# drum_circuits.net
KiCad netlist of a schematic drawn in EAGLE
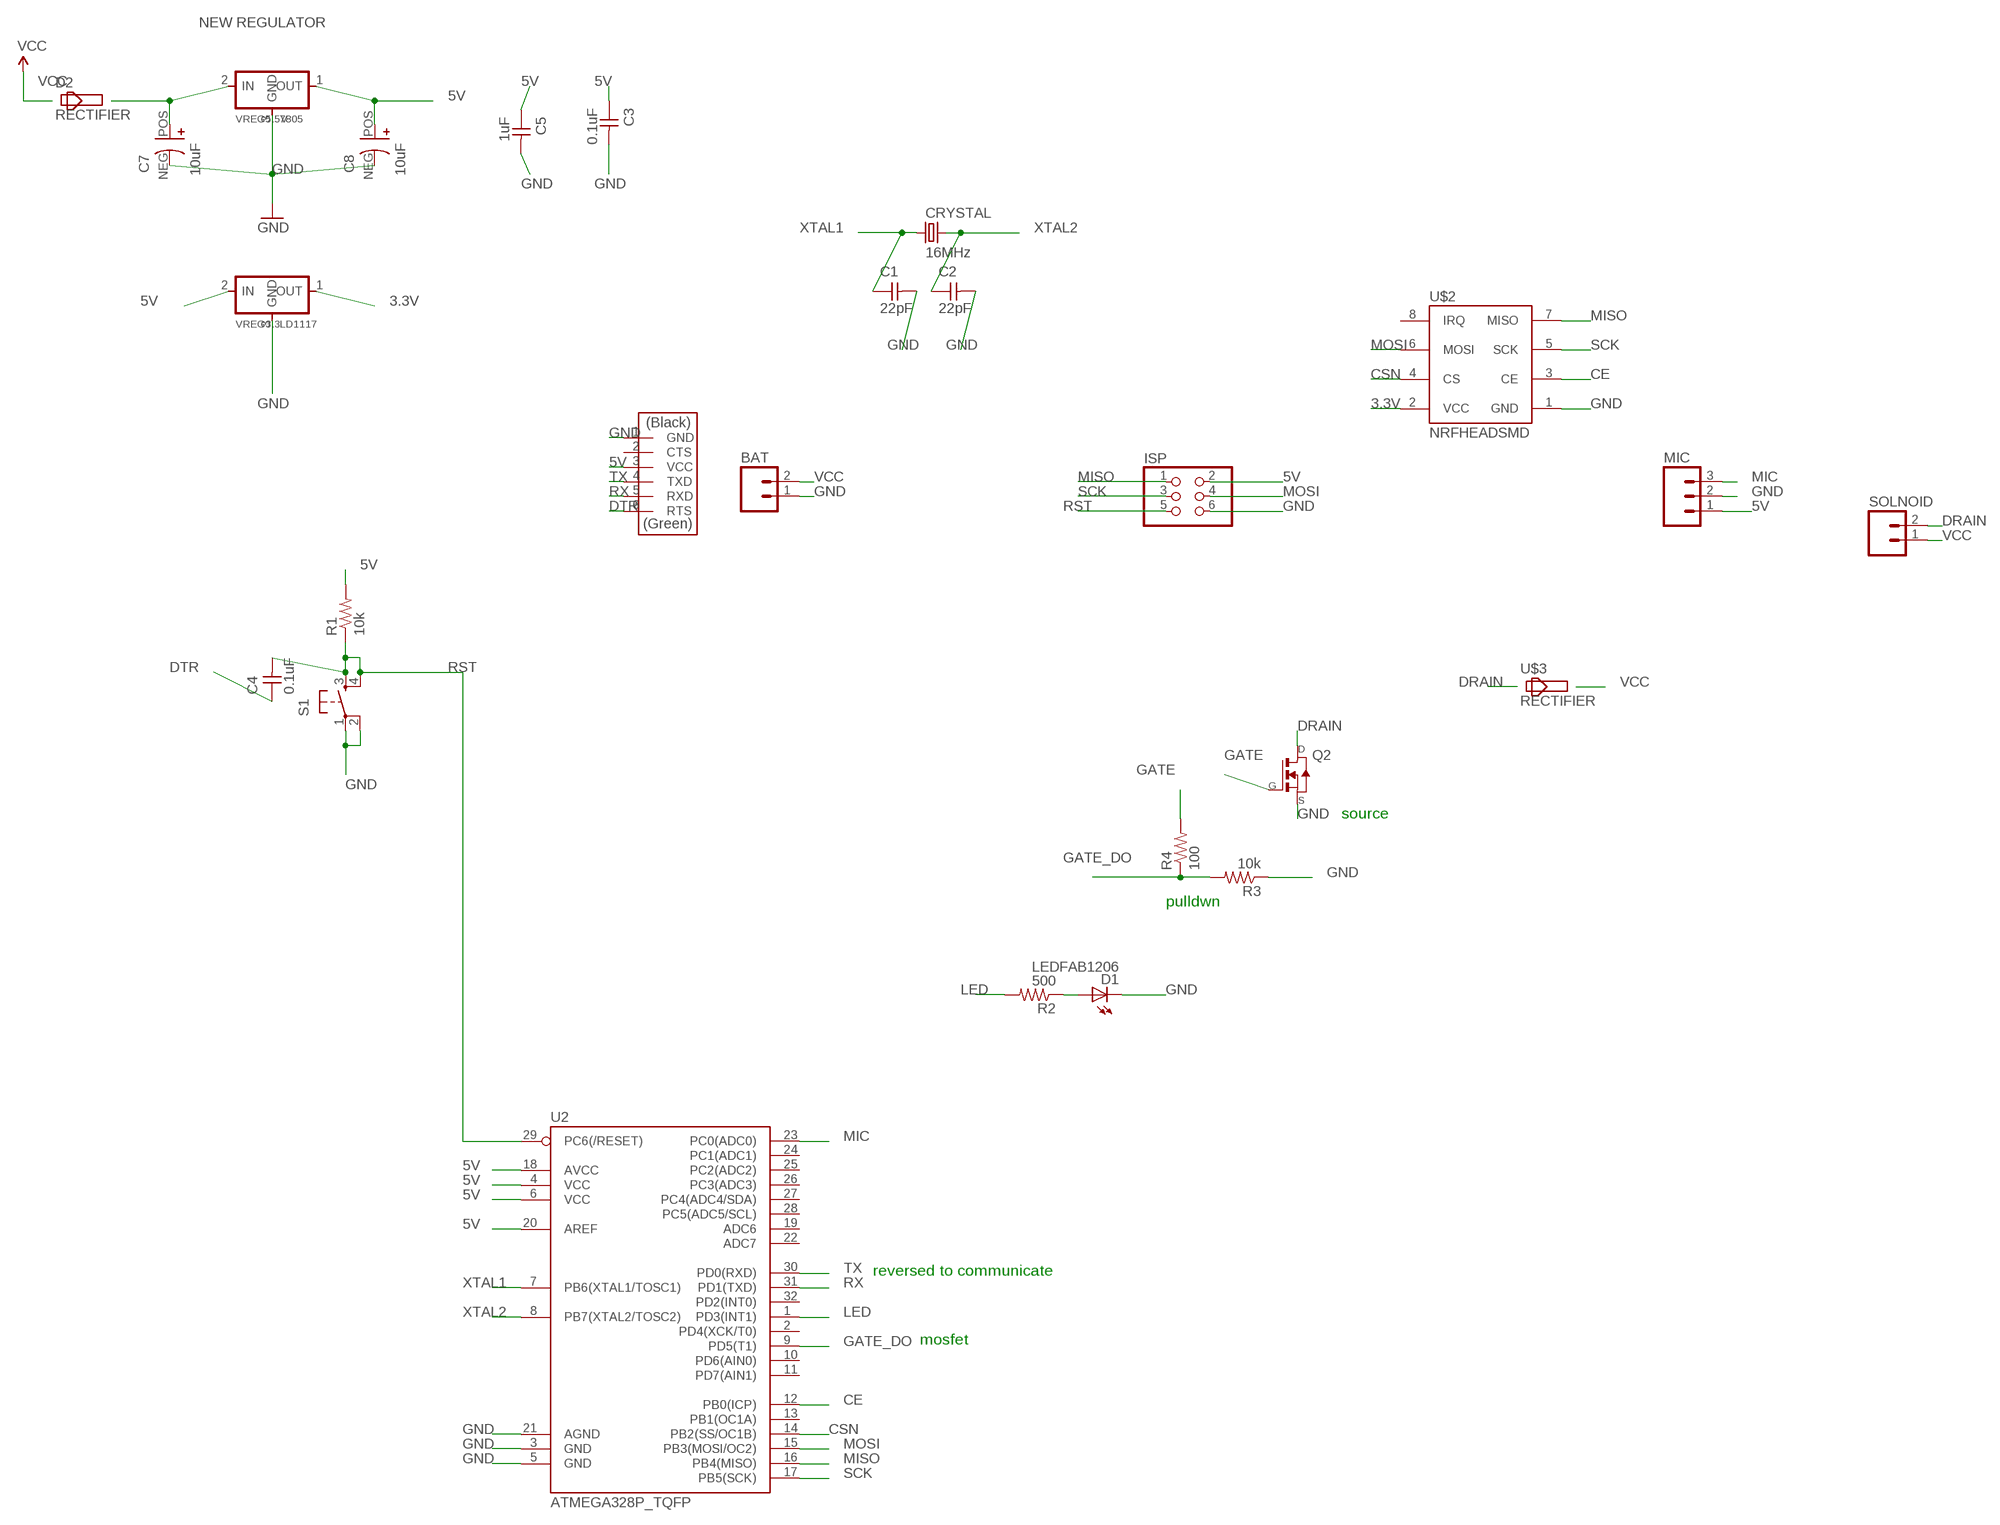
[diagram p0: schematic, sheet 1]

(export (version "E")
  (design (tool "Eeschema 10.0.6"))
  (components
    (comp (ref "BAT")
      (value "M02PTH")
      (footprint "eagle-import:1X02")
      (libsource (lib "eagle-import") (part "M02PTH"))
    )
    (comp (ref "C1")
      (value "22pF")
      (footprint "eagle-import:C1206FAB")
      (libsource (lib "eagle-import") (part "CAP-UNPOLARIZEDFAB"))
    )
    (comp (ref "C2")
      (value "22pF")
      (footprint "eagle-import:C1206FAB")
      (libsource (lib "eagle-import") (part "CAP-UNPOLARIZEDFAB"))
    )
    (comp (ref "C3")
      (value "0.1uF")
      (footprint "eagle-import:C1206FAB")
      (libsource (lib "eagle-import") (part "CAP-UNPOLARIZEDFAB"))
    )
    (comp (ref "C4")
      (value "0.1uF")
      (footprint "eagle-import:C1206FAB")
      (libsource (lib "eagle-import") (part "CAP-UNPOLARIZEDFAB"))
    )
    (comp (ref "C5")
      (value "1uF")
      (footprint "eagle-import:C1206FAB")
      (libsource (lib "eagle-import") (part "CAP-UNPOLARIZEDFAB"))
    )
    (comp (ref "C7")
      (value "10uF")
      (footprint "eagle-import:PANASONIC-CAP-SMD-B")
      (libsource (lib "eagle-import") (part "POLCAP-PANASONIC-SMD-B01"))
    )
    (comp (ref "C8")
      (value "10uF")
      (footprint "eagle-import:PANASONIC-CAP-SMD-B")
      (libsource (lib "eagle-import") (part "POLCAP-PANASONIC-SMD-B01"))
    )
    (comp (ref "CRYSTAL")
      (value "16MHz")
      (footprint "eagle-import:2-SMD-5X3MM")
      (libsource (lib "eagle-import") (part "CRYSTAL"))
    )
    (comp (ref "D1")
      (value "LEDFAB1206")
      (footprint "eagle-import:LED1206FAB")
      (libsource (lib "eagle-import") (part "LEDFAB1206"))
    )
    (comp (ref "D2")
      (value "RECTIFIER")
      (footprint "eagle-import:RECTIFIER")
      (libsource (lib "eagle-import") (part "RECTIFIER"))
    )
    (comp (ref "ISP")
      (value "PINHD-2X3-SMD")
      (footprint "eagle-import:2X03SMD")
      (libsource (lib "eagle-import") (part "PINHD-2X3-SMD"))
    )
    (comp (ref "MIC")
      (value "M03PTH")
      (footprint "eagle-import:1X03")
      (libsource (lib "eagle-import") (part "M03PTH"))
    )
    (comp (ref "Q2")
      (value "NMOSFETSOT23")
      (footprint "eagle-import:SOT-23")
      (libsource (lib "eagle-import") (part "NMOSFETSOT23"))
    )
    (comp (ref "R1")
      (value "10k")
      (footprint "eagle-import:R1206FAB")
      (libsource (lib "eagle-import") (part "RES-US1206FAB"))
    )
    (comp (ref "R2")
      (value "500")
      (footprint "eagle-import:R1206FAB")
      (libsource (lib "eagle-import") (part "RES-US1206FAB"))
    )
    (comp (ref "R3")
      (value "10k")
      (footprint "eagle-import:R1206FAB")
      (libsource (lib "eagle-import") (part "RES-US1206FAB"))
    )
    (comp (ref "R4")
      (value "100")
      (footprint "eagle-import:R1206FAB")
      (libsource (lib "eagle-import") (part "RES-US1206FAB"))
    )
    (comp (ref "S1")
      (value "6MM_SWITCH6MM_SWITCH")
      (footprint "eagle-import:6MM_SWITCH")
      (libsource (lib "eagle-import") (part "6MM_SWITCH6MM_SWITCH"))
    )
    (comp (ref "SOLNOID")
      (value "M02PTH")
      (footprint "eagle-import:1X02")
      (libsource (lib "eagle-import") (part "M02PTH"))
    )
    (comp (ref "U$1")
      (value "FTDI-SMD-HEADER")
      (footprint "eagle-import:1X06SMD")
      (libsource (lib "eagle-import") (part "FTDI-SMD-HEADER"))
    )
    (comp (ref "U$2")
      (value "NRFHEADSMD")
      (footprint "eagle-import:2.54MM")
      (libsource (lib "eagle-import") (part "NRFHEADSMD"))
    )
    (comp (ref "U$3")
      (value "RECTIFIER")
      (footprint "eagle-import:RECTIFIER")
      (libsource (lib "eagle-import") (part "RECTIFIER"))
    )
    (comp (ref "U2")
      (value "ATMEGA328P_TQFP")
      (footprint "eagle-import:TQFP32-08")
      (libsource (lib "eagle-import") (part "ATMEGA328P_TQFP"))
    )
    (comp (ref "VREG3.3")
      (value "LD1117")
      (footprint "eagle-import:SOT23")
      (libsource (lib "eagle-import") (part "REGULATORSOT23"))
    )
    (comp (ref "VREG5.5V")
      (value "7805")
      (footprint "eagle-import:SOT23")
      (libsource (lib "eagle-import") (part "REGULATORSOT23"))
    )
  )
  (nets
    (net (code "1") (name "/3.3V") (class "Default")
      (node (ref "U$2") (pin "2") (pinfunction "VCC_2") (pintype "bidirectional"))
      (node (ref "VREG3.3") (pin "1") (pinfunction "OUT_1") (pintype "bidirectional"))
    )
    (net (code "2") (name "/5V") (class "Default")
      (node (ref "C3") (pin "1") (pinfunction "1_1") (pintype "passive"))
      (node (ref "C5") (pin "1") (pinfunction "1_1") (pintype "passive"))
      (node (ref "C8") (pin "POS") (pinfunction "+_POS") (pintype "bidirectional"))
      (node (ref "ISP") (pin "2") (pinfunction "2_2") (pintype "passive"))
      (node (ref "MIC") (pin "1") (pinfunction "1_1") (pintype "passive"))
      (node (ref "R1") (pin "2") (pinfunction "2_2") (pintype "passive"))
      (node (ref "U$1") (pin "3") (pinfunction "VCC_3") (pintype "bidirectional"))
      (node (ref "U2") (pin "18") (pinfunction "AVCC_18") (pintype "bidirectional"))
      (node (ref "U2") (pin "20") (pinfunction "AREF_20") (pintype "bidirectional"))
      (node (ref "U2") (pin "4") (pinfunction "VCC_4") (pintype "bidirectional"))
      (node (ref "U2") (pin "6") (pinfunction "VCC_6") (pintype "bidirectional"))
      (node (ref "VREG3.3") (pin "2") (pinfunction "IN_2") (pintype "bidirectional"))
      (node (ref "VREG5.5V") (pin "1") (pinfunction "OUT_1") (pintype "bidirectional"))
    )
    (net (code "3") (name "/CE") (class "Default")
      (node (ref "U$2") (pin "3") (pinfunction "CE_3") (pintype "bidirectional"))
      (node (ref "U2") (pin "12") (pinfunction "PB0(ICP)_12") (pintype "bidirectional"))
    )
    (net (code "4") (name "/CSN") (class "Default")
      (node (ref "U$2") (pin "4") (pinfunction "CS_4") (pintype "bidirectional"))
      (node (ref "U2") (pin "14") (pinfunction "PB2(SS/OC1B)_14") (pintype "bidirectional"))
    )
    (net (code "5") (name "/DRAIN") (class "Default")
      (node (ref "Q2") (pin "1") (pinfunction "D_1") (pintype "passive"))
      (node (ref "SOLNOID") (pin "2") (pinfunction "2_2") (pintype "passive"))
      (node (ref "U$3") (pin "1") (pinfunction "1_1") (pintype "bidirectional"))
    )
    (net (code "6") (name "/DTR") (class "Default")
      (node (ref "C4") (pin "1") (pinfunction "1_1") (pintype "passive"))
      (node (ref "U$1") (pin "6") (pinfunction "RTS_6") (pintype "bidirectional"))
    )
    (net (code "7") (name "/GATE") (class "Default")
      (node (ref "Q2") (pin "3") (pinfunction "G_3") (pintype "passive"))
      (node (ref "R4") (pin "2") (pinfunction "2_2") (pintype "passive"))
    )
    (net (code "8") (name "/GATE_DO") (class "Default")
      (node (ref "R3") (pin "2") (pinfunction "2_2") (pintype "passive"))
      (node (ref "R4") (pin "1") (pinfunction "1_1") (pintype "passive"))
      (node (ref "U2") (pin "9") (pinfunction "PD5(T1)_9") (pintype "bidirectional"))
    )
    (net (code "9") (name "/LED") (class "Default")
      (node (ref "R2") (pin "2") (pinfunction "2_2") (pintype "passive"))
      (node (ref "U2") (pin "1") (pinfunction "PD3(INT1)_1") (pintype "bidirectional"))
    )
    (net (code "10") (name "/MIC") (class "Default")
      (node (ref "MIC") (pin "3") (pinfunction "3_3") (pintype "passive"))
      (node (ref "U2") (pin "23") (pinfunction "PC0(ADC0)_23") (pintype "bidirectional"))
    )
    (net (code "11") (name "/MISO") (class "Default")
      (node (ref "ISP") (pin "1") (pinfunction "1_1") (pintype "passive"))
      (node (ref "U$2") (pin "7") (pinfunction "MISO_7") (pintype "bidirectional"))
      (node (ref "U2") (pin "16") (pinfunction "PB4(MISO)_16") (pintype "bidirectional"))
    )
    (net (code "12") (name "/MOSI") (class "Default")
      (node (ref "ISP") (pin "4") (pinfunction "4_4") (pintype "passive"))
      (node (ref "U$2") (pin "6") (pinfunction "MOSI_6") (pintype "bidirectional"))
      (node (ref "U2") (pin "15") (pinfunction "PB3(MOSI/OC2)_15") (pintype "bidirectional"))
    )
    (net (code "13") (name "/RST") (class "Default")
      (node (ref "C4") (pin "2") (pinfunction "2_2") (pintype "passive"))
      (node (ref "ISP") (pin "5") (pinfunction "5_5") (pintype "passive"))
      (node (ref "R1") (pin "1") (pinfunction "1_1") (pintype "passive"))
      (node (ref "S1") (pin "3") (pinfunction "S_3") (pintype "passive"))
      (node (ref "S1") (pin "4") (pinfunction "S1_4") (pintype "passive"))
      (node (ref "U2") (pin "29") (pinfunction "PC6(/RESET)_29") (pintype "bidirectional"))
    )
    (net (code "14") (name "/RX") (class "Default")
      (node (ref "U$1") (pin "5") (pinfunction "RXD_5") (pintype "bidirectional"))
      (node (ref "U2") (pin "31") (pinfunction "PD1(TXD)_31") (pintype "bidirectional"))
    )
    (net (code "15") (name "/SCK") (class "Default")
      (node (ref "ISP") (pin "3") (pinfunction "3_3") (pintype "passive"))
      (node (ref "U$2") (pin "5") (pinfunction "SCK_5") (pintype "bidirectional"))
      (node (ref "U2") (pin "17") (pinfunction "PB5(SCK)_17") (pintype "bidirectional"))
    )
    (net (code "16") (name "/TX") (class "Default")
      (node (ref "U$1") (pin "4") (pinfunction "TXD_4") (pintype "bidirectional"))
      (node (ref "U2") (pin "30") (pinfunction "PD0(RXD)_30") (pintype "bidirectional"))
    )
    (net (code "17") (name "/XTAL1") (class "Default")
      (node (ref "C1") (pin "1") (pinfunction "1_1") (pintype "passive"))
      (node (ref "CRYSTAL") (pin "P$1") (pinfunction "1_P$1") (pintype "passive"))
      (node (ref "U2") (pin "7") (pinfunction "PB6(XTAL1/TOSC1)_7") (pintype "bidirectional"))
    )
    (net (code "18") (name "/XTAL2") (class "Default")
      (node (ref "C2") (pin "1") (pinfunction "1_1") (pintype "passive"))
      (node (ref "CRYSTAL") (pin "P$2") (pinfunction "2_P$2") (pintype "passive"))
      (node (ref "U2") (pin "8") (pinfunction "PB7(XTAL2/TOSC2)_8") (pintype "bidirectional"))
    )
    (net (code "19") (name "GND") (class "Default")
      (node (ref "BAT") (pin "1") (pinfunction "1_1") (pintype "passive"))
      (node (ref "C1") (pin "2") (pinfunction "2_2") (pintype "passive"))
      (node (ref "C2") (pin "2") (pinfunction "2_2") (pintype "passive"))
      (node (ref "C3") (pin "2") (pinfunction "2_2") (pintype "passive"))
      (node (ref "C5") (pin "2") (pinfunction "2_2") (pintype "passive"))
      (node (ref "C7") (pin "NEG") (pinfunction "-_NEG") (pintype "bidirectional"))
      (node (ref "C8") (pin "NEG") (pinfunction "-_NEG") (pintype "bidirectional"))
      (node (ref "D1") (pin "2") (pinfunction "C_2") (pintype "passive"))
      (node (ref "ISP") (pin "6") (pinfunction "6_6") (pintype "passive"))
      (node (ref "MIC") (pin "2") (pinfunction "2_2") (pintype "passive"))
      (node (ref "Q2") (pin "2") (pinfunction "S_2") (pintype "passive"))
      (node (ref "R3") (pin "1") (pinfunction "1_1") (pintype "passive"))
      (node (ref "S1") (pin "1") (pinfunction "P_1") (pintype "passive"))
      (node (ref "S1") (pin "2") (pinfunction "P1_2") (pintype "passive"))
      (node (ref "U$1") (pin "1") (pinfunction "GND_1") (pintype "bidirectional"))
      (node (ref "U$2") (pin "1") (pinfunction "GND_1") (pintype "bidirectional"))
      (node (ref "U2") (pin "21") (pinfunction "AGND_21") (pintype "bidirectional"))
      (node (ref "U2") (pin "3") (pinfunction "GND_3") (pintype "bidirectional"))
      (node (ref "U2") (pin "5") (pinfunction "GND_5") (pintype "bidirectional"))
      (node (ref "VREG3.3") (pin "3") (pinfunction "GND_3") (pintype "bidirectional"))
      (node (ref "VREG5.5V") (pin "3") (pinfunction "GND_3") (pintype "bidirectional"))
    )
    (net (code "20") (name "Net-(C7-+)") (class "Default")
      (node (ref "C7") (pin "POS") (pinfunction "+_POS") (pintype "bidirectional"))
      (node (ref "D2") (pin "2") (pinfunction "2_2") (pintype "bidirectional"))
      (node (ref "VREG5.5V") (pin "2") (pinfunction "IN_2") (pintype "bidirectional"))
    )
    (net (code "21") (name "Net-(D1-A)") (class "Default")
      (node (ref "D1") (pin "1") (pinfunction "A_1") (pintype "passive"))
      (node (ref "R2") (pin "1") (pinfunction "1_1") (pintype "passive"))
    )
    (net (code "22") (name "VCC") (class "Default")
      (node (ref "BAT") (pin "2") (pinfunction "2_2") (pintype "passive"))
      (node (ref "D2") (pin "1") (pinfunction "1_1") (pintype "bidirectional"))
      (node (ref "SOLNOID") (pin "1") (pinfunction "1_1") (pintype "passive"))
      (node (ref "U$3") (pin "2") (pinfunction "2_2") (pintype "bidirectional"))
    )
    (net (code "23") (name "unconnected-(U$1-CTS-Pad2)") (class "Default")
      (node (ref "U$1") (pin "2") (pinfunction "CTS_2") (pintype "bidirectional"))
    )
    (net (code "24") (name "unconnected-(U$2-IRQ-Pad8)") (class "Default")
      (node (ref "U$2") (pin "8") (pinfunction "IRQ_8") (pintype "bidirectional"))
    )
    (net (code "25") (name "unconnected-(U2-ADC6-Pad19)") (class "Default")
      (node (ref "U2") (pin "19") (pinfunction "ADC6_19") (pintype "bidirectional"))
    )
    (net (code "26") (name "unconnected-(U2-ADC7-Pad22)") (class "Default")
      (node (ref "U2") (pin "22") (pinfunction "ADC7_22") (pintype "bidirectional"))
    )
    (net (code "27") (name "unconnected-(U2-PB1(OC1A)-Pad13)") (class "Default")
      (node (ref "U2") (pin "13") (pinfunction "PB1(OC1A)_13") (pintype "bidirectional"))
    )
    (net (code "28") (name "unconnected-(U2-PC1(ADC1)-Pad24)") (class "Default")
      (node (ref "U2") (pin "24") (pinfunction "PC1(ADC1)_24") (pintype "bidirectional"))
    )
    (net (code "29") (name "unconnected-(U2-PC2(ADC2)-Pad25)") (class "Default")
      (node (ref "U2") (pin "25") (pinfunction "PC2(ADC2)_25") (pintype "bidirectional"))
    )
    (net (code "30") (name "unconnected-(U2-PC3(ADC3)-Pad26)") (class "Default")
      (node (ref "U2") (pin "26") (pinfunction "PC3(ADC3)_26") (pintype "bidirectional"))
    )
    (net (code "31") (name "unconnected-(U2-PC4(ADC4{slash}SDA)-Pad27)") (class "Default")
      (node (ref "U2") (pin "27") (pinfunction "PC4(ADC4/SDA)_27") (pintype "bidirectional"))
    )
    (net (code "32") (name "unconnected-(U2-PC5(ADC5{slash}SCL)-Pad28)") (class "Default")
      (node (ref "U2") (pin "28") (pinfunction "PC5(ADC5/SCL)_28") (pintype "bidirectional"))
    )
    (net (code "33") (name "unconnected-(U2-PD2(INT0)-Pad32)") (class "Default")
      (node (ref "U2") (pin "32") (pinfunction "PD2(INT0)_32") (pintype "bidirectional"))
    )
    (net (code "34") (name "unconnected-(U2-PD4(XCK{slash}T0)-Pad2)") (class "Default")
      (node (ref "U2") (pin "2") (pinfunction "PD4(XCK/T0)_2") (pintype "bidirectional"))
    )
    (net (code "35") (name "unconnected-(U2-PD6(AIN0)-Pad10)") (class "Default")
      (node (ref "U2") (pin "10") (pinfunction "PD6(AIN0)_10") (pintype "bidirectional"))
    )
    (net (code "36") (name "unconnected-(U2-PD7(AIN1)-Pad11)") (class "Default")
      (node (ref "U2") (pin "11") (pinfunction "PD7(AIN1)_11") (pintype "bidirectional"))
    )
  )
)
